# TutorialA.net
KiCad netlist of a schematic drawn in EAGLE
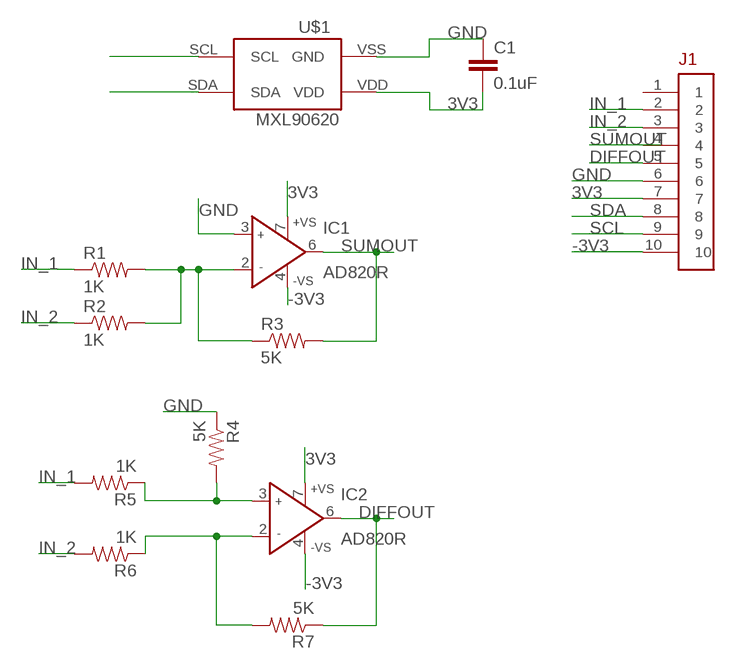
[diagram p0: schematic, sheet 1]

(export (version "E")
  (design (tool "Eeschema 10.0.6"))
  (components
    (comp (ref "C1")
      (value "0.1uF")
      (footprint "eagle-import:0805")
      (libsource (lib "eagle-import") (part "CAP0805"))
    )
    (comp (ref "IC1")
      (value "AD820R")
      (footprint "eagle-import:SO8")
      (libsource (lib "eagle-import") (part "AD820R"))
    )
    (comp (ref "IC2")
      (value "AD820R")
      (footprint "eagle-import:SO8")
      (libsource (lib "eagle-import") (part "AD820R"))
    )
    (comp (ref "J1")
      (value "M50-3120545")
      (footprint "eagle-import:10PINFEMALE")
      (libsource (lib "eagle-import") (part "M50-3120545"))
    )
    (comp (ref "R1")
      (value "1K")
      (footprint "eagle-import:0805")
      (libsource (lib "eagle-import") (part "RESISTOR"))
    )
    (comp (ref "R2")
      (value "1K")
      (footprint "eagle-import:0805")
      (libsource (lib "eagle-import") (part "RESISTOR"))
    )
    (comp (ref "R3")
      (value "5K")
      (footprint "eagle-import:0805")
      (libsource (lib "eagle-import") (part "RESISTOR"))
    )
    (comp (ref "R4")
      (value "5K")
      (footprint "eagle-import:0805")
      (libsource (lib "eagle-import") (part "RESISTOR"))
    )
    (comp (ref "R5")
      (value "1K")
      (footprint "eagle-import:0805")
      (libsource (lib "eagle-import") (part "RESISTOR"))
    )
    (comp (ref "R6")
      (value "1K")
      (footprint "eagle-import:0805")
      (libsource (lib "eagle-import") (part "RESISTOR"))
    )
    (comp (ref "R7")
      (value "5K")
      (footprint "eagle-import:0805")
      (libsource (lib "eagle-import") (part "RESISTOR"))
    )
    (comp (ref "U$1")
      (value "MXL90620")
      (footprint "eagle-import:MXL90620")
      (libsource (lib "eagle-import") (part "MXL90620"))
    )
  )
  (nets
    (net (code "1") (name "/-3V3") (class "Default")
      (node (ref "IC1") (pin "4") (pinfunction "-VS_4") (pintype "input"))
      (node (ref "IC2") (pin "4") (pinfunction "-VS_4") (pintype "input"))
      (node (ref "J1") (pin "10") (pinfunction "10_10") (pintype "bidirectional"))
    )
    (net (code "2") (name "/3V3") (class "Default")
      (node (ref "C1") (pin "2") (pinfunction "2_2") (pintype "passive"))
      (node (ref "IC1") (pin "7") (pinfunction "+VS_7") (pintype "input"))
      (node (ref "IC2") (pin "7") (pinfunction "+VS_7") (pintype "input"))
      (node (ref "J1") (pin "7") (pinfunction "7_7") (pintype "bidirectional"))
      (node (ref "U$1") (pin "VDD") (pinfunction "VDD_VDD") (pintype "bidirectional"))
    )
    (net (code "3") (name "/DIFFOUT") (class "Default")
      (node (ref "IC2") (pin "6") (pinfunction "OUT_6") (pintype "output"))
      (node (ref "J1") (pin "5") (pinfunction "5_5") (pintype "bidirectional"))
      (node (ref "R7") (pin "1") (pinfunction "1_1") (pintype "passive"))
    )
    (net (code "4") (name "/GND") (class "Default")
      (node (ref "C1") (pin "1") (pinfunction "1_1") (pintype "passive"))
      (node (ref "IC1") (pin "3") (pinfunction "IN+_3") (pintype "input"))
      (node (ref "J1") (pin "6") (pinfunction "6_6") (pintype "bidirectional"))
      (node (ref "R4") (pin "1") (pinfunction "1_1") (pintype "passive"))
      (node (ref "U$1") (pin "VSS") (pinfunction "GND_VSS") (pintype "bidirectional"))
    )
    (net (code "5") (name "/IN_1") (class "Default")
      (node (ref "J1") (pin "2") (pinfunction "2_2") (pintype "bidirectional"))
      (node (ref "R1") (pin "1") (pinfunction "1_1") (pintype "passive"))
      (node (ref "R5") (pin "2") (pinfunction "2_2") (pintype "passive"))
    )
    (net (code "6") (name "/IN_2") (class "Default")
      (node (ref "J1") (pin "3") (pinfunction "3_3") (pintype "bidirectional"))
      (node (ref "R2") (pin "1") (pinfunction "1_1") (pintype "passive"))
      (node (ref "R6") (pin "2") (pinfunction "2_2") (pintype "passive"))
    )
    (net (code "7") (name "/SCL") (class "Default")
      (node (ref "J1") (pin "9") (pinfunction "9_9") (pintype "bidirectional"))
      (node (ref "U$1") (pin "SCL") (pinfunction "SCL_SCL") (pintype "bidirectional"))
    )
    (net (code "8") (name "/SDA") (class "Default")
      (node (ref "J1") (pin "8") (pinfunction "8_8") (pintype "bidirectional"))
      (node (ref "U$1") (pin "SDA") (pinfunction "SDA_SDA") (pintype "bidirectional"))
    )
    (net (code "9") (name "/SUMOUT") (class "Default")
      (node (ref "IC1") (pin "6") (pinfunction "OUT_6") (pintype "output"))
      (node (ref "R3") (pin "2") (pinfunction "2_2") (pintype "passive"))
    )
    (net (code "10") (name "Net-(IC1-IN-)") (class "Default")
      (node (ref "IC1") (pin "2") (pinfunction "IN-_2") (pintype "input"))
      (node (ref "R1") (pin "2") (pinfunction "2_2") (pintype "passive"))
      (node (ref "R2") (pin "2") (pinfunction "2_2") (pintype "passive"))
      (node (ref "R3") (pin "1") (pinfunction "1_1") (pintype "passive"))
    )
    (net (code "11") (name "Net-(IC2-IN+)") (class "Default")
      (node (ref "IC2") (pin "3") (pinfunction "IN+_3") (pintype "input"))
      (node (ref "R4") (pin "2") (pinfunction "2_2") (pintype "passive"))
      (node (ref "R5") (pin "1") (pinfunction "1_1") (pintype "passive"))
    )
    (net (code "12") (name "Net-(IC2-IN-)") (class "Default")
      (node (ref "IC2") (pin "2") (pinfunction "IN-_2") (pintype "input"))
      (node (ref "R6") (pin "1") (pinfunction "1_1") (pintype "passive"))
      (node (ref "R7") (pin "2") (pinfunction "2_2") (pintype "passive"))
    )
    (net (code "13") (name "unconnected-(J1-Pad1)") (class "Default")
      (node (ref "J1") (pin "1") (pinfunction "1_1") (pintype "bidirectional"))
    )
    (net (code "14") (name "unconnected-(J1-Pad4)") (class "Default")
      (node (ref "J1") (pin "4") (pinfunction "4_4") (pintype "bidirectional"))
    )
  )
)
